# Guide_laser.net
KiCad netlist of a schematic drawn in Altium Designer
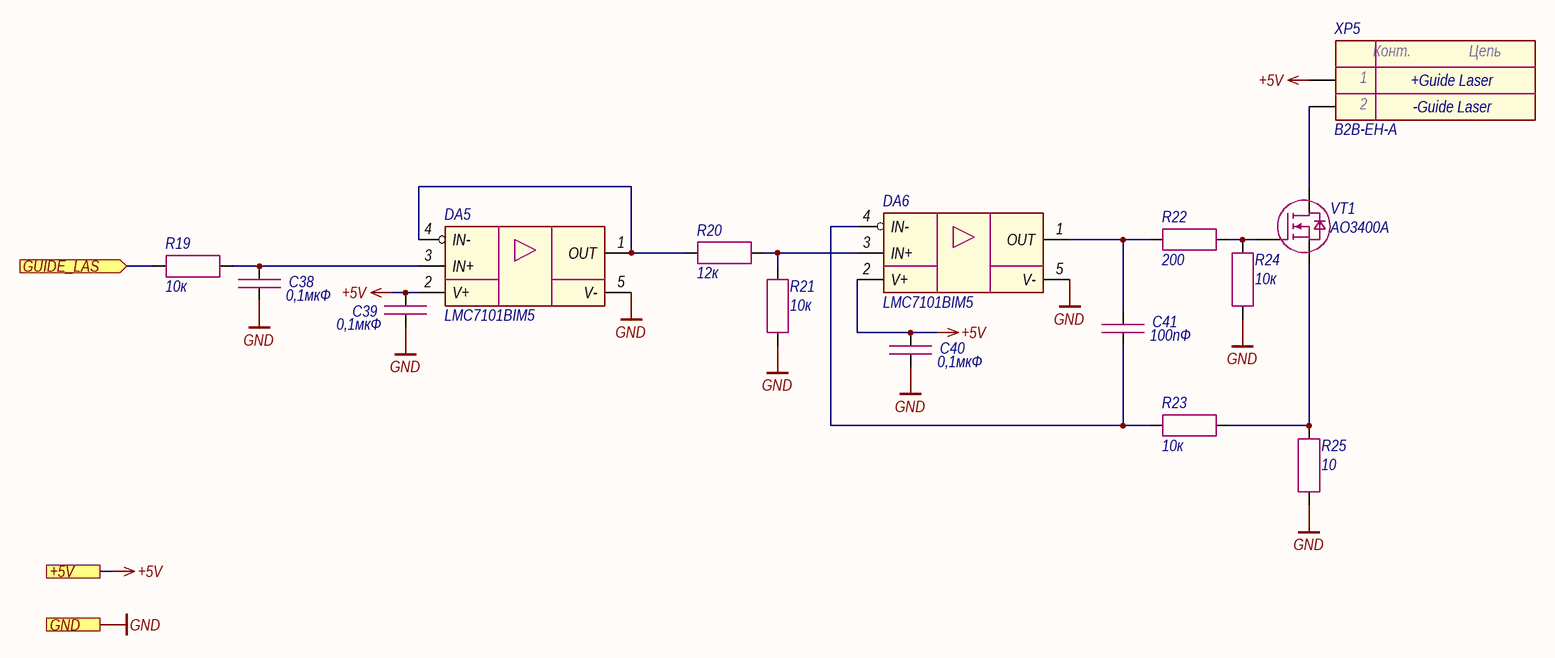
[diagram p0: Guide_laser.SchDoc]

(export (version "E")
  (design (tool "Eeschema 10.0.6"))
  (components
    (comp (ref "C38")
      (value "0,1мкФ")
      (footprint "Pcb_library:CAP_0603")
      (fields (field (name "MANUFACTURER") "Murata"))
      (libsource (lib "Schem_library") (part "Capacitor"))
    )
    (comp (ref "C39")
      (value "0,1мкФ")
      (footprint "Pcb_library:CAP_0603")
      (fields (field (name "MANUFACTURER") "Murata"))
      (libsource (lib "Schem_library") (part "Capacitor"))
    )
    (comp (ref "C40")
      (value "0,1мкФ")
      (footprint "Pcb_library:CAP_0603")
      (fields (field (name "MANUFACTURER") "Murata"))
      (libsource (lib "Schem_library") (part "Capacitor"))
    )
    (comp (ref "C41")
      (value "100пФ")
      (footprint "Pcb_library:CAP_0603")
      (fields (field (name "MANUFACTURER") "Murata"))
      (libsource (lib "Schem_library") (part "Capacitor"))
    )
    (comp (ref "DA5")
      (value "LMC7101BIM5")
      (footprint "Pcb_library:SOT-23-5")
      (fields (field (name "MANUFACTURER") "Texas Instruments"))
      (libsource (lib "Schem_library") (part "LMC7101"))
    )
    (comp (ref "DA6")
      (value "LMC7101BIM5")
      (footprint "Pcb_library:SOT-23-5")
      (fields (field (name "MANUFACTURER") "Texas Instruments"))
      (libsource (lib "Schem_library") (part "LMC7101"))
    )
    (comp (ref "R19")
      (value "10к")
      (footprint "Pcb_library:RES_0603")
      (fields (field (name "MANUFACTURER") "Yageo"))
      (libsource (lib "Schem_library") (part "Resistor"))
    )
    (comp (ref "R20")
      (value "12к")
      (footprint "Pcb_library:RES_0603")
      (fields (field (name "MANUFACTURER") "Yageo"))
      (libsource (lib "Schem_library") (part "Resistor"))
    )
    (comp (ref "R21")
      (value "10к")
      (footprint "Pcb_library:RES_0603")
      (fields (field (name "MANUFACTURER") "Yageo"))
      (libsource (lib "Schem_library") (part "Resistor"))
    )
    (comp (ref "R22")
      (value "200")
      (footprint "Pcb_library:RES_0603")
      (fields (field (name "MANUFACTURER") "Yageo"))
      (libsource (lib "Schem_library") (part "Resistor"))
    )
    (comp (ref "R23")
      (value "10к")
      (footprint "Pcb_library:RES_0603")
      (fields (field (name "MANUFACTURER") "Yageo"))
      (libsource (lib "Schem_library") (part "Resistor"))
    )
    (comp (ref "R24")
      (value "10к")
      (footprint "Pcb_library:RES_0603")
      (fields (field (name "MANUFACTURER") "Yageo"))
      (libsource (lib "Schem_library") (part "Resistor"))
    )
    (comp (ref "R25")
      (value "10")
      (footprint "Pcb_library:RES_1210")
      (fields (field (name "MANUFACTURER") "Yageo"))
      (libsource (lib "Schem_library") (part "Resistor"))
    )
    (comp (ref "VT1")
      (value "AO3400A")
      (footprint "Pcb_library:SOT-23-3")
      (fields (field (name "MANUFACTURER") "UMW"))
      (libsource (lib "Schem_library") (part "MOSFET N-channel"))
    )
    (comp (ref "XP5")
      (value "B2B-EH-A")
      (footprint "Pcb_library:B2B-EH-A")
      (fields (field (name "MANUFACTURER") "JST"))
      (libsource (lib "Schem_library") (part "Connector-2"))
    )
  )
  (nets
    (net (code "1") (name "+5V") (class "Default")
      (node (ref "C39") (pin "1") (pinfunction "1_1") (pintype "passive"))
      (node (ref "C40") (pin "1") (pinfunction "1_1") (pintype "passive"))
      (node (ref "DA5") (pin "2") (pinfunction "V+_2") (pintype "passive"))
      (node (ref "DA6") (pin "2") (pinfunction "V+_2") (pintype "passive"))
      (node (ref "XP5") (pin "1") (pintype "passive"))
    )
    (net (code "2") (name "/GUIDE_LAS") (class "Default")
      (node (ref "R19") (pin "1") (pinfunction "1_1") (pintype "passive"))
    )
    (net (code "3") (name "GND") (class "Default")
      (node (ref "C38") (pin "2") (pinfunction "2_2") (pintype "passive"))
      (node (ref "C39") (pin "2") (pinfunction "2_2") (pintype "passive"))
      (node (ref "C40") (pin "2") (pinfunction "2_2") (pintype "passive"))
      (node (ref "DA5") (pin "5") (pinfunction "V-_5") (pintype "passive"))
      (node (ref "DA6") (pin "5") (pinfunction "V-_5") (pintype "passive"))
      (node (ref "R21") (pin "2") (pinfunction "2_2") (pintype "passive"))
      (node (ref "R24") (pin "1") (pinfunction "1_1") (pintype "passive"))
      (node (ref "R25") (pin "1") (pinfunction "1_1") (pintype "passive"))
    )
    (net (code "4") (name "Net-(DA5-IN+)") (class "Default")
      (node (ref "C38") (pin "1") (pinfunction "1_1") (pintype "passive"))
      (node (ref "DA5") (pin "3") (pinfunction "IN+_3") (pintype "passive"))
      (node (ref "R19") (pin "2") (pinfunction "2_2") (pintype "passive"))
    )
    (net (code "5") (name "Net-(DA5-IN-)") (class "Default")
      (node (ref "DA5") (pin "1") (pinfunction "OUT_1") (pintype "passive"))
      (node (ref "DA5") (pin "4") (pinfunction "IN-_4") (pintype "passive"))
      (node (ref "R20") (pin "1") (pinfunction "1_1") (pintype "passive"))
    )
    (net (code "6") (name "Net-(DA6-IN+)") (class "Default")
      (node (ref "DA6") (pin "3") (pinfunction "IN+_3") (pintype "passive"))
      (node (ref "R20") (pin "2") (pinfunction "2_2") (pintype "passive"))
      (node (ref "R21") (pin "1") (pinfunction "1_1") (pintype "passive"))
    )
    (net (code "7") (name "Net-(DA6-IN-)") (class "Default")
      (node (ref "C41") (pin "2") (pinfunction "2_2") (pintype "passive"))
      (node (ref "DA6") (pin "4") (pinfunction "IN-_4") (pintype "passive"))
      (node (ref "R23") (pin "1") (pinfunction "1_1") (pintype "passive"))
    )
    (net (code "8") (name "Net-(DA6-OUT)") (class "Default")
      (node (ref "C41") (pin "1") (pinfunction "1_1") (pintype "passive"))
      (node (ref "DA6") (pin "1") (pinfunction "OUT_1") (pintype "passive"))
      (node (ref "R22") (pin "1") (pinfunction "1_1") (pintype "passive"))
    )
    (net (code "9") (name "Net-(VT1-D)") (class "Default")
      (node (ref "VT1") (pin "3") (pinfunction "D_3") (pintype "passive"))
      (node (ref "XP5") (pin "2") (pintype "passive"))
    )
    (net (code "10") (name "Net-(VT1-G)") (class "Default")
      (node (ref "R22") (pin "2") (pinfunction "2_2") (pintype "passive"))
      (node (ref "R24") (pin "2") (pinfunction "2_2") (pintype "passive"))
      (node (ref "VT1") (pin "1") (pinfunction "G_1") (pintype "passive"))
    )
    (net (code "11") (name "Net-(VT1-S)") (class "Default")
      (node (ref "R23") (pin "2") (pinfunction "2_2") (pintype "passive"))
      (node (ref "R25") (pin "2") (pinfunction "2_2") (pintype "passive"))
      (node (ref "VT1") (pin "2") (pinfunction "S_2") (pintype "passive"))
    )
  )
)
